# HBridge.net
KiCad netlist of a schematic drawn in EAGLE
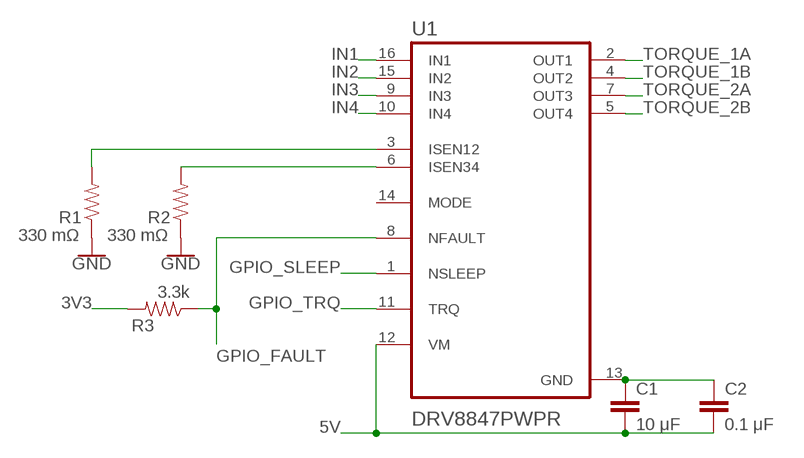
[diagram p0: schematic, sheet 1]

(export (version "E")
  (design (tool "Eeschema 10.0.6"))
  (components
    (comp (ref "C1")
      (value "10 μF")
      (footprint "eagle-import:0805")
      (libsource (lib "eagle-import") (part "CAP0805"))
    )
    (comp (ref "C2")
      (value "0.1 μF")
      (footprint "eagle-import:0805")
      (libsource (lib "eagle-import") (part "CAP0805"))
    )
    (comp (ref "R1")
      (value "330 mΩ")
      (footprint "eagle-import:0805")
      (libsource (lib "eagle-import") (part "RESISTOR0805-RES"))
    )
    (comp (ref "R2")
      (value "330 mΩ")
      (footprint "eagle-import:0805")
      (libsource (lib "eagle-import") (part "RESISTOR0805-RES"))
    )
    (comp (ref "R3")
      (value "3.3k")
      (footprint "eagle-import:0805")
      (libsource (lib "eagle-import") (part "RESISTOR0805-RES"))
    )
    (comp (ref "U1")
      (value "DRV8847PWPR")
      (footprint "eagle-import:SOP65P640X120-17N")
      (fields (field (name "MF") "Texas Instruments"))
      (libsource (lib "eagle-import") (part "DRV8847PWPR"))
    )
  )
  (nets
    (net (code "1") (name "/3V3") (class "Default")
      (node (ref "R3") (pin "2") (pinfunction "2_2") (pintype "passive"))
    )
    (net (code "2") (name "/5V") (class "Default")
      (node (ref "C1") (pin "2") (pinfunction "2_2") (pintype "passive"))
      (node (ref "C2") (pin "2") (pinfunction "2_2") (pintype "passive"))
      (node (ref "U1") (pin "12") (pinfunction "VM_12") (pintype "bidirectional"))
    )
    (net (code "3") (name "/GPIO_FAULT") (class "Default")
      (node (ref "R3") (pin "1") (pinfunction "1_1") (pintype "passive"))
      (node (ref "U1") (pin "8") (pinfunction "NFAULT_8") (pintype "bidirectional"))
    )
    (net (code "4") (name "/GPIO_SLEEP") (class "Default")
      (node (ref "U1") (pin "1") (pinfunction "NSLEEP_1") (pintype "bidirectional"))
    )
    (net (code "5") (name "/GPIO_TRQ") (class "Default")
      (node (ref "U1") (pin "11") (pinfunction "TRQ_11") (pintype "bidirectional"))
    )
    (net (code "6") (name "/IN1") (class "Default")
      (node (ref "U1") (pin "16") (pinfunction "IN1_16") (pintype "input"))
    )
    (net (code "7") (name "/IN2") (class "Default")
      (node (ref "U1") (pin "15") (pinfunction "IN2_15") (pintype "input"))
    )
    (net (code "8") (name "/IN3") (class "Default")
      (node (ref "U1") (pin "9") (pinfunction "IN3_9") (pintype "input"))
    )
    (net (code "9") (name "/IN4") (class "Default")
      (node (ref "U1") (pin "10") (pinfunction "IN4_10") (pintype "input"))
    )
    (net (code "10") (name "/TORQUE_1A") (class "Default")
      (node (ref "U1") (pin "2") (pinfunction "OUT1_2") (pintype "output"))
    )
    (net (code "11") (name "/TORQUE_1B") (class "Default")
      (node (ref "U1") (pin "4") (pinfunction "OUT2_4") (pintype "output"))
    )
    (net (code "12") (name "/TORQUE_2A") (class "Default")
      (node (ref "U1") (pin "7") (pinfunction "OUT3_7") (pintype "output"))
    )
    (net (code "13") (name "/TORQUE_2B") (class "Default")
      (node (ref "U1") (pin "5") (pinfunction "OUT4_5") (pintype "output"))
    )
    (net (code "14") (name "GND") (class "Default")
      (node (ref "R1") (pin "1") (pinfunction "1_1") (pintype "passive"))
      (node (ref "R2") (pin "1") (pinfunction "1_1") (pintype "passive"))
    )
    (net (code "15") (name "Net-(U1-GND)") (class "Default")
      (node (ref "C1") (pin "1") (pinfunction "1_1") (pintype "passive"))
      (node (ref "C2") (pin "1") (pinfunction "1_1") (pintype "passive"))
      (node (ref "U1") (pin "13") (pinfunction "GND_13") (pintype "power_in"))
    )
    (net (code "16") (name "Net-(U1-ISEN12)") (class "Default")
      (node (ref "R1") (pin "2") (pinfunction "2_2") (pintype "passive"))
      (node (ref "U1") (pin "3") (pinfunction "ISEN12_3") (pintype "bidirectional"))
    )
    (net (code "17") (name "Net-(U1-ISEN34)") (class "Default")
      (node (ref "R2") (pin "2") (pinfunction "2_2") (pintype "passive"))
      (node (ref "U1") (pin "6") (pinfunction "ISEN34_6") (pintype "bidirectional"))
    )
    (net (code "18") (name "unconnected-(U1-MODE-Pad14)") (class "Default")
      (node (ref "U1") (pin "14") (pinfunction "MODE_14") (pintype "bidirectional"))
    )
  )
)
